# PixelLeaf_RP2040.net
KiCad netlist of a schematic drawn in EAGLE
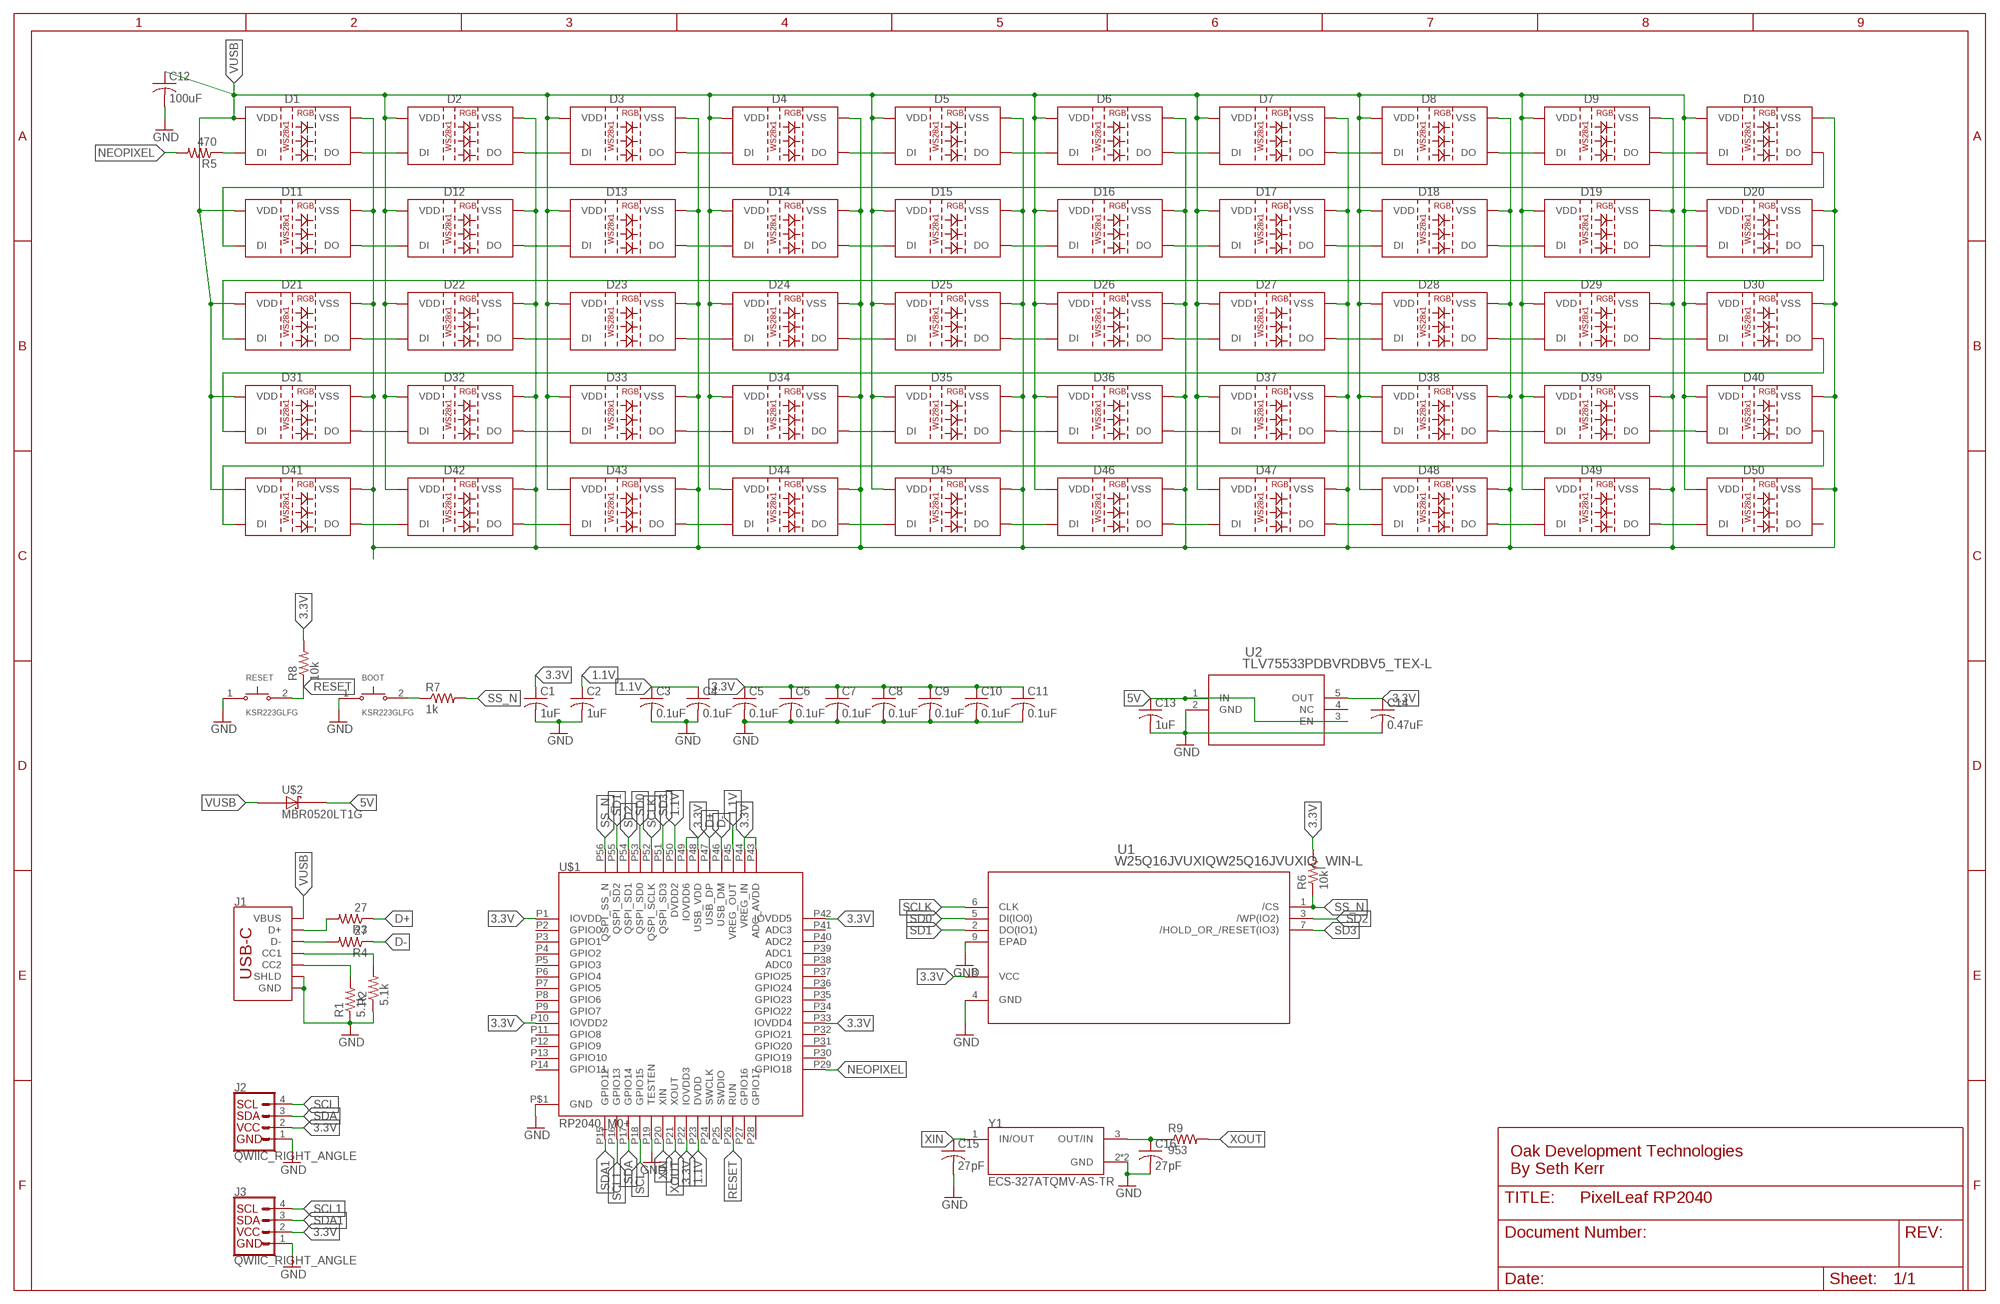
[diagram p0: schematic, sheet 1]

(export (version "E")
  (design (tool "Eeschema 10.0.6"))
  (components
    (comp (ref "BOOT")
      (value "KSR223GLFG")
      (footprint "eagle-import:SW_KSR223GLFG")
      (fields (field (name "MF") "C&K"))
      (libsource (lib "eagle-import") (part "KSR223GLFG"))
    )
    (comp (ref "C1")
      (value "1uF")
      (footprint "eagle-import:C0603")
      (libsource (lib "eagle-import") (part "C-USC0603"))
    )
    (comp (ref "C2")
      (value "1uF")
      (footprint "eagle-import:C0603")
      (libsource (lib "eagle-import") (part "C-USC0603"))
    )
    (comp (ref "C3")
      (value "0.1uF")
      (footprint "eagle-import:C0603")
      (libsource (lib "eagle-import") (part "C-USC0603"))
    )
    (comp (ref "C4")
      (value "0.1uF")
      (footprint "eagle-import:C0603")
      (libsource (lib "eagle-import") (part "C-USC0603"))
    )
    (comp (ref "C5")
      (value "0.1uF")
      (footprint "eagle-import:C0603")
      (libsource (lib "eagle-import") (part "C-USC0603"))
    )
    (comp (ref "C6")
      (value "0.1uF")
      (footprint "eagle-import:C0603")
      (libsource (lib "eagle-import") (part "C-USC0603"))
    )
    (comp (ref "C7")
      (value "0.1uF")
      (footprint "eagle-import:C0603")
      (libsource (lib "eagle-import") (part "C-USC0603"))
    )
    (comp (ref "C8")
      (value "0.1uF")
      (footprint "eagle-import:C0603")
      (libsource (lib "eagle-import") (part "C-USC0603"))
    )
    (comp (ref "C9")
      (value "0.1uF")
      (footprint "eagle-import:C0603")
      (libsource (lib "eagle-import") (part "C-USC0603"))
    )
    (comp (ref "C10")
      (value "0.1uF")
      (footprint "eagle-import:C0603")
      (libsource (lib "eagle-import") (part "C-USC0603"))
    )
    (comp (ref "C11")
      (value "0.1uF")
      (footprint "eagle-import:C0603")
      (libsource (lib "eagle-import") (part "C-USC0603"))
    )
    (comp (ref "C12")
      (value "100uF")
      (footprint "eagle-import:C1206")
      (libsource (lib "eagle-import") (part "C-USC1206"))
    )
    (comp (ref "C13")
      (value "1uF")
      (footprint "eagle-import:C0603")
      (libsource (lib "eagle-import") (part "C-USC0603"))
    )
    (comp (ref "C14")
      (value "0.47uF")
      (footprint "eagle-import:C0603")
      (libsource (lib "eagle-import") (part "C-USC0603"))
    )
    (comp (ref "C15")
      (value "27pF")
      (footprint "eagle-import:C0402")
      (libsource (lib "eagle-import") (part "C-USC0402"))
    )
    (comp (ref "C16")
      (value "27pF")
      (footprint "eagle-import:C0402")
      (libsource (lib "eagle-import") (part "C-USC0402"))
    )
    (comp (ref "D1")
      (value "WS2812BWS2812B-3535")
      (footprint "eagle-import:WS2812-3535")
      (libsource (lib "eagle-import") (part "WS2812BWS2812B-3535"))
    )
    (comp (ref "D2")
      (value "WS2812BWS2812B-3535")
      (footprint "eagle-import:WS2812-3535")
      (libsource (lib "eagle-import") (part "WS2812BWS2812B-3535"))
    )
    (comp (ref "D3")
      (value "WS2812BWS2812B-3535")
      (footprint "eagle-import:WS2812-3535")
      (libsource (lib "eagle-import") (part "WS2812BWS2812B-3535"))
    )
    (comp (ref "D4")
      (value "WS2812BWS2812B-3535")
      (footprint "eagle-import:WS2812-3535")
      (libsource (lib "eagle-import") (part "WS2812BWS2812B-3535"))
    )
    (comp (ref "D5")
      (value "WS2812BWS2812B-3535")
      (footprint "eagle-import:WS2812-3535")
      (libsource (lib "eagle-import") (part "WS2812BWS2812B-3535"))
    )
    (comp (ref "D6")
      (value "WS2812BWS2812B-3535")
      (footprint "eagle-import:WS2812-3535")
      (libsource (lib "eagle-import") (part "WS2812BWS2812B-3535"))
    )
    (comp (ref "D7")
      (value "WS2812BWS2812B-3535")
      (footprint "eagle-import:WS2812-3535")
      (libsource (lib "eagle-import") (part "WS2812BWS2812B-3535"))
    )
    (comp (ref "D8")
      (value "WS2812BWS2812B-3535")
      (footprint "eagle-import:WS2812-3535")
      (libsource (lib "eagle-import") (part "WS2812BWS2812B-3535"))
    )
    (comp (ref "D9")
      (value "WS2812BWS2812B-3535")
      (footprint "eagle-import:WS2812-3535")
      (libsource (lib "eagle-import") (part "WS2812BWS2812B-3535"))
    )
    (comp (ref "D10")
      (value "WS2812BWS2812B-3535")
      (footprint "eagle-import:WS2812-3535")
      (libsource (lib "eagle-import") (part "WS2812BWS2812B-3535"))
    )
    (comp (ref "D11")
      (value "WS2812BWS2812B-3535")
      (footprint "eagle-import:WS2812-3535")
      (libsource (lib "eagle-import") (part "WS2812BWS2812B-3535"))
    )
    (comp (ref "D12")
      (value "WS2812BWS2812B-3535")
      (footprint "eagle-import:WS2812-3535")
      (libsource (lib "eagle-import") (part "WS2812BWS2812B-3535"))
    )
    (comp (ref "D13")
      (value "WS2812BWS2812B-3535")
      (footprint "eagle-import:WS2812-3535")
      (libsource (lib "eagle-import") (part "WS2812BWS2812B-3535"))
    )
    (comp (ref "D14")
      (value "WS2812BWS2812B-3535")
      (footprint "eagle-import:WS2812-3535")
      (libsource (lib "eagle-import") (part "WS2812BWS2812B-3535"))
    )
    (comp (ref "D15")
      (value "WS2812BWS2812B-3535")
      (footprint "eagle-import:WS2812-3535")
      (libsource (lib "eagle-import") (part "WS2812BWS2812B-3535"))
    )
    (comp (ref "D16")
      (value "WS2812BWS2812B-3535")
      (footprint "eagle-import:WS2812-3535")
      (libsource (lib "eagle-import") (part "WS2812BWS2812B-3535"))
    )
    (comp (ref "D17")
      (value "WS2812BWS2812B-3535")
      (footprint "eagle-import:WS2812-3535")
      (libsource (lib "eagle-import") (part "WS2812BWS2812B-3535"))
    )
    (comp (ref "D18")
      (value "WS2812BWS2812B-3535")
      (footprint "eagle-import:WS2812-3535")
      (libsource (lib "eagle-import") (part "WS2812BWS2812B-3535"))
    )
    (comp (ref "D19")
      (value "WS2812BWS2812B-3535")
      (footprint "eagle-import:WS2812-3535")
      (libsource (lib "eagle-import") (part "WS2812BWS2812B-3535"))
    )
    (comp (ref "D20")
      (value "WS2812BWS2812B-3535")
      (footprint "eagle-import:WS2812-3535")
      (libsource (lib "eagle-import") (part "WS2812BWS2812B-3535"))
    )
    (comp (ref "D21")
      (value "WS2812BWS2812B-3535")
      (footprint "eagle-import:WS2812-3535")
      (libsource (lib "eagle-import") (part "WS2812BWS2812B-3535"))
    )
    (comp (ref "D22")
      (value "WS2812BWS2812B-3535")
      (footprint "eagle-import:WS2812-3535")
      (libsource (lib "eagle-import") (part "WS2812BWS2812B-3535"))
    )
    (comp (ref "D23")
      (value "WS2812BWS2812B-3535")
      (footprint "eagle-import:WS2812-3535")
      (libsource (lib "eagle-import") (part "WS2812BWS2812B-3535"))
    )
    (comp (ref "D24")
      (value "WS2812BWS2812B-3535")
      (footprint "eagle-import:WS2812-3535")
      (libsource (lib "eagle-import") (part "WS2812BWS2812B-3535"))
    )
    (comp (ref "D25")
      (value "WS2812BWS2812B-3535")
      (footprint "eagle-import:WS2812-3535")
      (libsource (lib "eagle-import") (part "WS2812BWS2812B-3535"))
    )
    (comp (ref "D26")
      (value "WS2812BWS2812B-3535")
      (footprint "eagle-import:WS2812-3535")
      (libsource (lib "eagle-import") (part "WS2812BWS2812B-3535"))
    )
    (comp (ref "D27")
      (value "WS2812BWS2812B-3535")
      (footprint "eagle-import:WS2812-3535")
      (libsource (lib "eagle-import") (part "WS2812BWS2812B-3535"))
    )
    (comp (ref "D28")
      (value "WS2812BWS2812B-3535")
      (footprint "eagle-import:WS2812-3535")
      (libsource (lib "eagle-import") (part "WS2812BWS2812B-3535"))
    )
    (comp (ref "D29")
      (value "WS2812BWS2812B-3535")
      (footprint "eagle-import:WS2812-3535")
      (libsource (lib "eagle-import") (part "WS2812BWS2812B-3535"))
    )
    (comp (ref "D30")
      (value "WS2812BWS2812B-3535")
      (footprint "eagle-import:WS2812-3535")
      (libsource (lib "eagle-import") (part "WS2812BWS2812B-3535"))
    )
    (comp (ref "D31")
      (value "WS2812BWS2812B-3535")
      (footprint "eagle-import:WS2812-3535")
      (libsource (lib "eagle-import") (part "WS2812BWS2812B-3535"))
    )
    (comp (ref "D32")
      (value "WS2812BWS2812B-3535")
      (footprint "eagle-import:WS2812-3535")
      (libsource (lib "eagle-import") (part "WS2812BWS2812B-3535"))
    )
    (comp (ref "D33")
      (value "WS2812BWS2812B-3535")
      (footprint "eagle-import:WS2812-3535")
      (libsource (lib "eagle-import") (part "WS2812BWS2812B-3535"))
    )
    (comp (ref "D34")
      (value "WS2812BWS2812B-3535")
      (footprint "eagle-import:WS2812-3535")
      (libsource (lib "eagle-import") (part "WS2812BWS2812B-3535"))
    )
    (comp (ref "D35")
      (value "WS2812BWS2812B-3535")
      (footprint "eagle-import:WS2812-3535")
      (libsource (lib "eagle-import") (part "WS2812BWS2812B-3535"))
    )
    (comp (ref "D36")
      (value "WS2812BWS2812B-3535")
      (footprint "eagle-import:WS2812-3535")
      (libsource (lib "eagle-import") (part "WS2812BWS2812B-3535"))
    )
    (comp (ref "D37")
      (value "WS2812BWS2812B-3535")
      (footprint "eagle-import:WS2812-3535")
      (libsource (lib "eagle-import") (part "WS2812BWS2812B-3535"))
    )
    (comp (ref "D38")
      (value "WS2812BWS2812B-3535")
      (footprint "eagle-import:WS2812-3535")
      (libsource (lib "eagle-import") (part "WS2812BWS2812B-3535"))
    )
    (comp (ref "D39")
      (value "WS2812BWS2812B-3535")
      (footprint "eagle-import:WS2812-3535")
      (libsource (lib "eagle-import") (part "WS2812BWS2812B-3535"))
    )
    (comp (ref "D40")
      (value "WS2812BWS2812B-3535")
      (footprint "eagle-import:WS2812-3535")
      (libsource (lib "eagle-import") (part "WS2812BWS2812B-3535"))
    )
    (comp (ref "D41")
      (value "WS2812BWS2812B-3535")
      (footprint "eagle-import:WS2812-3535")
      (libsource (lib "eagle-import") (part "WS2812BWS2812B-3535"))
    )
    (comp (ref "D42")
      (value "WS2812BWS2812B-3535")
      (footprint "eagle-import:WS2812-3535")
      (libsource (lib "eagle-import") (part "WS2812BWS2812B-3535"))
    )
    (comp (ref "D43")
      (value "WS2812BWS2812B-3535")
      (footprint "eagle-import:WS2812-3535")
      (libsource (lib "eagle-import") (part "WS2812BWS2812B-3535"))
    )
    (comp (ref "D44")
      (value "WS2812BWS2812B-3535")
      (footprint "eagle-import:WS2812-3535")
      (libsource (lib "eagle-import") (part "WS2812BWS2812B-3535"))
    )
    (comp (ref "D45")
      (value "WS2812BWS2812B-3535")
      (footprint "eagle-import:WS2812-3535")
      (libsource (lib "eagle-import") (part "WS2812BWS2812B-3535"))
    )
    (comp (ref "D46")
      (value "WS2812BWS2812B-3535")
      (footprint "eagle-import:WS2812-3535")
      (libsource (lib "eagle-import") (part "WS2812BWS2812B-3535"))
    )
    (comp (ref "D47")
      (value "WS2812BWS2812B-3535")
      (footprint "eagle-import:WS2812-3535")
      (libsource (lib "eagle-import") (part "WS2812BWS2812B-3535"))
    )
    (comp (ref "D48")
      (value "WS2812BWS2812B-3535")
      (footprint "eagle-import:WS2812-3535")
      (libsource (lib "eagle-import") (part "WS2812BWS2812B-3535"))
    )
    (comp (ref "D49")
      (value "WS2812BWS2812B-3535")
      (footprint "eagle-import:WS2812-3535")
      (libsource (lib "eagle-import") (part "WS2812BWS2812B-3535"))
    )
    (comp (ref "D50")
      (value "WS2812BWS2812B-3535")
      (footprint "eagle-import:WS2812-3535")
      (libsource (lib "eagle-import") (part "WS2812BWS2812B-3535"))
    )
    (comp (ref "J1")
      (value "USB_C_2-LAYER_PADS")
      (footprint "eagle-import:USB-C-16P-2LAYER-PADS")
      (libsource (lib "eagle-import") (part "USB_C_2-LAYER_PADS"))
    )
    (comp (ref "J2")
      (value "QWIIC_RIGHT_ANGLE")
      (footprint "eagle-import:JST04_1MM_RA")
      (libsource (lib "eagle-import") (part "QWIIC_CONNECTORJS-1MM"))
    )
    (comp (ref "J3")
      (value "QWIIC_RIGHT_ANGLE")
      (footprint "eagle-import:JST04_1MM_RA")
      (libsource (lib "eagle-import") (part "QWIIC_CONNECTORJS-1MM"))
    )
    (comp (ref "R1")
      (value "5.1k")
      (footprint "eagle-import:R0603")
      (libsource (lib "eagle-import") (part "R-US_R0603"))
    )
    (comp (ref "R2")
      (value "5.1k")
      (footprint "eagle-import:R0603")
      (libsource (lib "eagle-import") (part "R-US_R0603"))
    )
    (comp (ref "R3")
      (value "27")
      (footprint "eagle-import:R0603")
      (libsource (lib "eagle-import") (part "R-US_R0603"))
    )
    (comp (ref "R4")
      (value "27")
      (footprint "eagle-import:R0603")
      (libsource (lib "eagle-import") (part "R-US_R0603"))
    )
    (comp (ref "R5")
      (value "470")
      (footprint "eagle-import:R0603")
      (libsource (lib "eagle-import") (part "R-US_R0603"))
    )
    (comp (ref "R6")
      (value "10k")
      (footprint "eagle-import:R0603")
      (libsource (lib "eagle-import") (part "R-US_R0603"))
    )
    (comp (ref "R7")
      (value "1k")
      (footprint "eagle-import:R0603")
      (libsource (lib "eagle-import") (part "R-US_R0603"))
    )
    (comp (ref "R8")
      (value "10k")
      (footprint "eagle-import:R0603")
      (libsource (lib "eagle-import") (part "R-US_R0603"))
    )
    (comp (ref "R9")
      (value "953")
      (footprint "eagle-import:R0402")
      (libsource (lib "eagle-import") (part "R-US_R0402"))
    )
    (comp (ref "RESET")
      (value "KSR223GLFG")
      (footprint "eagle-import:SW_KSR223GLFG")
      (fields (field (name "MF") "C&K"))
      (libsource (lib "eagle-import") (part "KSR223GLFG"))
    )
    (comp (ref "U$1")
      (value "RP2040_M0+")
      (footprint "eagle-import:QFN-56")
      (libsource (lib "eagle-import") (part "RP2040_M0+"))
    )
    (comp (ref "U$2")
      (value "MBR0520LT1G")
      (footprint "eagle-import:SOD3716X117(SOD-123)")
      (fields (field (name "MF") "ON Semiconductor"))
      (libsource (lib "eagle-import") (part "MBR0520LT1G"))
    )
    (comp (ref "U1")
      (value "W25Q16JVUXIQW25Q16JVUXIQ_WIN-L")
      (footprint "eagle-import:W25Q16JVUXIQ_WIN-L")
      (fields
        (field (name "MANUFACTURER_PART_NUMBER") "W25Q16JVUXIQ")
        (field (name "COPYRIGHT") "Copyright (C) 2018 Accelerated Designs. All rights reserved")
      )
      (libsource (lib "eagle-import") (part "W25Q16JVUXIQW25Q16JVUXIQ_WIN-L"))
    )
    (comp (ref "U2")
      (value "TLV75533PDBVRDBV5_TEX-L")
      (footprint "eagle-import:DBV5_TEX-L")
      (fields
        (field (name "MANUFACTURER_PART_NUMBER") "TLV75533PDBVR")
        (field (name "COPYRIGHT") "Copyright (C) 2018 Accelerated Designs. All rights reserved")
      )
      (libsource (lib "eagle-import") (part "TLV75533PDBVRDBV5_TEX-L"))
    )
    (comp (ref "Y1")
      (value "ECS-327ATQMV-AS-TR")
      (footprint "eagle-import:XTAL_ECS-327ATQMV-AS-TR")
      (fields (field (name "DIGI-KEY_PART_NUMBER") "XC2826CT-ND") (field (name "MF") "ECS Inc."))
      (libsource (lib "eagle-import") (part "ECS-327ATQMV-AS-TR"))
    )
  )
  (nets
    (net (code "1") (name "1.1V") (class "Default")
      (node (ref "C2") (pin "1") (pinfunction "1_1") (pintype "passive"))
      (node (ref "C3") (pin "1") (pinfunction "1_1") (pintype "passive"))
      (node (ref "C4") (pin "1") (pinfunction "1_1") (pintype "passive"))
      (node (ref "U$1") (pin "P23") (pinfunction "DVDD_P23") (pintype "bidirectional"))
      (node (ref "U$1") (pin "P45") (pinfunction "VREG_OUT_P45") (pintype "bidirectional"))
      (node (ref "U$1") (pin "P50") (pinfunction "DVDD2_P50") (pintype "bidirectional"))
    )
    (net (code "2") (name "3.3V") (class "Default")
      (node (ref "C1") (pin "1") (pinfunction "1_1") (pintype "passive"))
      (node (ref "C10") (pin "1") (pinfunction "1_1") (pintype "passive"))
      (node (ref "C11") (pin "1") (pinfunction "1_1") (pintype "passive"))
      (node (ref "C14") (pin "1") (pinfunction "1_1") (pintype "passive"))
      (node (ref "C5") (pin "1") (pinfunction "1_1") (pintype "passive"))
      (node (ref "C6") (pin "1") (pinfunction "1_1") (pintype "passive"))
      (node (ref "C7") (pin "1") (pinfunction "1_1") (pintype "passive"))
      (node (ref "C8") (pin "1") (pinfunction "1_1") (pintype "passive"))
      (node (ref "C9") (pin "1") (pinfunction "1_1") (pintype "passive"))
      (node (ref "J2") (pin "2") (pinfunction "2_2") (pintype "power_in"))
      (node (ref "J3") (pin "2") (pinfunction "2_2") (pintype "power_in"))
      (node (ref "R6") (pin "2") (pinfunction "2_2") (pintype "passive"))
      (node (ref "R8") (pin "2") (pinfunction "2_2") (pintype "passive"))
      (node (ref "U$1") (pin "P1") (pinfunction "IOVDD_P1") (pintype "bidirectional"))
      (node (ref "U$1") (pin "P10") (pinfunction "IOVDD2_P10") (pintype "bidirectional"))
      (node (ref "U$1") (pin "P22") (pinfunction "IOVDD3_P22") (pintype "bidirectional"))
      (node (ref "U$1") (pin "P33") (pinfunction "IOVDD4_P33") (pintype "bidirectional"))
      (node (ref "U$1") (pin "P42") (pinfunction "IOVDD5_P42") (pintype "bidirectional"))
      (node (ref "U$1") (pin "P43") (pinfunction "ADC_AVDD_P43") (pintype "bidirectional"))
      (node (ref "U$1") (pin "P44") (pinfunction "VREG_IN_P44") (pintype "bidirectional"))
      (node (ref "U$1") (pin "P48") (pinfunction "USB_VDD_P48") (pintype "bidirectional"))
      (node (ref "U$1") (pin "P49") (pinfunction "IOVDD6_P49") (pintype "bidirectional"))
      (node (ref "U1") (pin "8") (pinfunction "VCC_8") (pintype "passive"))
      (node (ref "U2") (pin "5") (pinfunction "OUT_5") (pintype "output"))
    )
    (net (code "3") (name "5V") (class "Default")
      (node (ref "C13") (pin "1") (pinfunction "1_1") (pintype "passive"))
      (node (ref "U$2") (pin "1") (pinfunction "C_1") (pintype "passive"))
      (node (ref "U2") (pin "1") (pinfunction "IN_1") (pintype "input"))
      (node (ref "U2") (pin "3") (pinfunction "EN_3") (pintype "input"))
    )
    (net (code "4") (name "D+") (class "Default")
      (node (ref "R3") (pin "1") (pinfunction "1_1") (pintype "passive"))
      (node (ref "U$1") (pin "P47") (pinfunction "USB_DP_P47") (pintype "bidirectional"))
    )
    (net (code "5") (name "D-") (class "Default")
      (node (ref "R4") (pin "1") (pinfunction "1_1") (pintype "passive"))
      (node (ref "U$1") (pin "P46") (pinfunction "USB_DM_P46") (pintype "bidirectional"))
    )
    (net (code "6") (name "GND") (class "Default")
      (node (ref "BOOT") (pin "1") (pinfunction "1_1") (pintype "passive"))
      (node (ref "C1") (pin "2") (pinfunction "2_2") (pintype "passive"))
      (node (ref "C10") (pin "2") (pinfunction "2_2") (pintype "passive"))
      (node (ref "C11") (pin "2") (pinfunction "2_2") (pintype "passive"))
      (node (ref "C12") (pin "2") (pinfunction "2_2") (pintype "passive"))
      (node (ref "C13") (pin "2") (pinfunction "2_2") (pintype "passive"))
      (node (ref "C14") (pin "2") (pinfunction "2_2") (pintype "passive"))
      (node (ref "C15") (pin "2") (pinfunction "2_2") (pintype "passive"))
      (node (ref "C16") (pin "2") (pinfunction "2_2") (pintype "passive"))
      (node (ref "C2") (pin "2") (pinfunction "2_2") (pintype "passive"))
      (node (ref "C3") (pin "2") (pinfunction "2_2") (pintype "passive"))
      (node (ref "C4") (pin "2") (pinfunction "2_2") (pintype "passive"))
      (node (ref "C5") (pin "2") (pinfunction "2_2") (pintype "passive"))
      (node (ref "C6") (pin "2") (pinfunction "2_2") (pintype "passive"))
      (node (ref "C7") (pin "2") (pinfunction "2_2") (pintype "passive"))
      (node (ref "C8") (pin "2") (pinfunction "2_2") (pintype "passive"))
      (node (ref "C9") (pin "2") (pinfunction "2_2") (pintype "passive"))
      (node (ref "D1") (pin "VSS") (pinfunction "VSS_VSS") (pintype "bidirectional"))
      (node (ref "D10") (pin "VSS") (pinfunction "VSS_VSS") (pintype "bidirectional"))
      (node (ref "D11") (pin "VSS") (pinfunction "VSS_VSS") (pintype "bidirectional"))
      (node (ref "D12") (pin "VSS") (pinfunction "VSS_VSS") (pintype "bidirectional"))
      (node (ref "D13") (pin "VSS") (pinfunction "VSS_VSS") (pintype "bidirectional"))
      (node (ref "D14") (pin "VSS") (pinfunction "VSS_VSS") (pintype "bidirectional"))
      (node (ref "D15") (pin "VSS") (pinfunction "VSS_VSS") (pintype "bidirectional"))
      (node (ref "D16") (pin "VSS") (pinfunction "VSS_VSS") (pintype "bidirectional"))
      (node (ref "D17") (pin "VSS") (pinfunction "VSS_VSS") (pintype "bidirectional"))
      (node (ref "D18") (pin "VSS") (pinfunction "VSS_VSS") (pintype "bidirectional"))
      (node (ref "D19") (pin "VSS") (pinfunction "VSS_VSS") (pintype "bidirectional"))
      (node (ref "D2") (pin "VSS") (pinfunction "VSS_VSS") (pintype "bidirectional"))
      (node (ref "D20") (pin "VSS") (pinfunction "VSS_VSS") (pintype "bidirectional"))
      (node (ref "D21") (pin "VSS") (pinfunction "VSS_VSS") (pintype "bidirectional"))
      (node (ref "D22") (pin "VSS") (pinfunction "VSS_VSS") (pintype "bidirectional"))
      (node (ref "D23") (pin "VSS") (pinfunction "VSS_VSS") (pintype "bidirectional"))
      (node (ref "D24") (pin "VSS") (pinfunction "VSS_VSS") (pintype "bidirectional"))
      (node (ref "D25") (pin "VSS") (pinfunction "VSS_VSS") (pintype "bidirectional"))
      (node (ref "D26") (pin "VSS") (pinfunction "VSS_VSS") (pintype "bidirectional"))
      (node (ref "D27") (pin "VSS") (pinfunction "VSS_VSS") (pintype "bidirectional"))
      (node (ref "D28") (pin "VSS") (pinfunction "VSS_VSS") (pintype "bidirectional"))
      (node (ref "D29") (pin "VSS") (pinfunction "VSS_VSS") (pintype "bidirectional"))
      (node (ref "D3") (pin "VSS") (pinfunction "VSS_VSS") (pintype "bidirectional"))
      (node (ref "D30") (pin "VSS") (pinfunction "VSS_VSS") (pintype "bidirectional"))
      (node (ref "D31") (pin "VSS") (pinfunction "VSS_VSS") (pintype "bidirectional"))
      (node (ref "D32") (pin "VSS") (pinfunction "VSS_VSS") (pintype "bidirectional"))
      (node (ref "D33") (pin "VSS") (pinfunction "VSS_VSS") (pintype "bidirectional"))
      (node (ref "D34") (pin "VSS") (pinfunction "VSS_VSS") (pintype "bidirectional"))
      (node (ref "D35") (pin "VSS") (pinfunction "VSS_VSS") (pintype "bidirectional"))
      (node (ref "D36") (pin "VSS") (pinfunction "VSS_VSS") (pintype "bidirectional"))
      (node (ref "D37") (pin "VSS") (pinfunction "VSS_VSS") (pintype "bidirectional"))
      (node (ref "D38") (pin "VSS") (pinfunction "VSS_VSS") (pintype "bidirectional"))
      (node (ref "D39") (pin "VSS") (pinfunction "VSS_VSS") (pintype "bidirectional"))
      (node (ref "D4") (pin "VSS") (pinfunction "VSS_VSS") (pintype "bidirectional"))
      (node (ref "D40") (pin "VSS") (pinfunction "VSS_VSS") (pintype "bidirectional"))
      (node (ref "D41") (pin "VSS") (pinfunction "VSS_VSS") (pintype "bidirectional"))
      (node (ref "D42") (pin "VSS") (pinfunction "VSS_VSS") (pintype "bidirectional"))
      (node (ref "D43") (pin "VSS") (pinfunction "VSS_VSS") (pintype "bidirectional"))
      (node (ref "D44") (pin "VSS") (pinfunction "VSS_VSS") (pintype "bidirectional"))
      (node (ref "D45") (pin "VSS") (pinfunction "VSS_VSS") (pintype "bidirectional"))
      (node (ref "D46") (pin "VSS") (pinfunction "VSS_VSS") (pintype "bidirectional"))
      (node (ref "D47") (pin "VSS") (pinfunction "VSS_VSS") (pintype "bidirectional"))
      (node (ref "D48") (pin "VSS") (pinfunction "VSS_VSS") (pintype "bidirectional"))
      (node (ref "D49") (pin "VSS") (pinfunction "VSS_VSS") (pintype "bidirectional"))
      (node (ref "D5") (pin "VSS") (pinfunction "VSS_VSS") (pintype "bidirectional"))
      (node (ref "D50") (pin "VSS") (pinfunction "VSS_VSS") (pintype "bidirectional"))
      (node (ref "D6") (pin "VSS") (pinfunction "VSS_VSS") (pintype "bidirectional"))
      (node (ref "D7") (pin "VSS") (pinfunction "VSS_VSS") (pintype "bidirectional"))
      (node (ref "D8") (pin "VSS") (pinfunction "VSS_VSS") (pintype "bidirectional"))
      (node (ref "D9") (pin "VSS") (pinfunction "VSS_VSS") (pintype "bidirectional"))
      (node (ref "J1") (pin "GND") (pinfunction "GND_GND") (pintype "bidirectional"))
      (node (ref "J1") (pin "GND2") (pinfunction "GND_GND2") (pintype "bidirectional"))
      (node (ref "J1") (pin "P$1") (pinfunction "SHLD_P$1") (pintype "bidirectional"))
      (node (ref "J1") (pin "P$2") (pinfunction "SHLD_P$2") (pintype "bidirectional"))
      (node (ref "J1") (pin "P$3") (pinfunction "SHLD_P$3") (pintype "bidirectional"))
      (node (ref "J1") (pin "P$4") (pinfunction "SHLD_P$4") (pintype "bidirectional"))
      (node (ref "J1") (pin "SHLD1") (pinfunction "SHLD_SHLD1") (pintype "bidirectional"))
      (node (ref "J1") (pin "SHLD2") (pinfunction "SHLD_SHLD2") (pintype "bidirectional"))
      (node (ref "J1") (pin "SHLD3") (pinfunction "SHLD_SHLD3") (pintype "bidirectional"))
      (node (ref "J1") (pin "SHLD4") (pinfunction "SHLD_SHLD4") (pintype "bidirectional"))
      (node (ref "J2") (pin "1") (pinfunction "1_1") (pintype "power_in"))
      (node (ref "J3") (pin "1") (pinfunction "1_1") (pintype "power_in"))
      (node (ref "R1") (pin "1") (pinfunction "1_1") (pintype "passive"))
      (node (ref "R2") (pin "1") (pinfunction "1_1") (pintype "passive"))
      (node (ref "RESET") (pin "1") (pinfunction "1_1") (pintype "passive"))
      (node (ref "U$1") (pin "P$1") (pinfunction "GND_P$1") (pintype "bidirectional"))
      (node (ref "U$1") (pin "P19") (pinfunction "TESTEN_P19") (pintype "bidirectional"))
      (node (ref "U1") (pin "4") (pinfunction "GND_4") (pintype "passive"))
      (node (ref "U1") (pin "9") (pinfunction "EPAD_9") (pintype "passive"))
      (node (ref "U2") (pin "2") (pinfunction "GND_2") (pintype "power_in"))
      (node (ref "Y1") (pin "2") (pinfunction "GND_2") (pintype "power_in"))
      (node (ref "Y1") (pin "4") (pinfunction "GND_4") (pintype "power_in"))
    )
    (net (code "7") (name "NEOPIXEL") (class "Default")
      (node (ref "R5") (pin "2") (pinfunction "2_2") (pintype "passive"))
      (node (ref "U$1") (pin "P29") (pinfunction "GPIO18_P29") (pintype "bidirectional"))
    )
    (net (code "8") (name "Net-(BOOT-Pad2)") (class "Default")
      (node (ref "BOOT") (pin "2") (pinfunction "2_2") (pintype "passive"))
      (node (ref "R7") (pin "1") (pinfunction "1_1") (pintype "passive"))
    )
    (net (code "9") (name "Net-(D1-DI)") (class "Default")
      (node (ref "D1") (pin "DIN") (pinfunction "DI_DIN") (pintype "bidirectional"))
      (node (ref "R5") (pin "1") (pinfunction "1_1") (pintype "passive"))
    )
    (net (code "10") (name "Net-(D1-DO)") (class "Default")
      (node (ref "D1") (pin "DOUT") (pinfunction "DO_DOUT") (pintype "bidirectional"))
      (node (ref "D2") (pin "DIN") (pinfunction "DI_DIN") (pintype "bidirectional"))
    )
    (net (code "11") (name "Net-(D2-DO)") (class "Default")
      (node (ref "D2") (pin "DOUT") (pinfunction "DO_DOUT") (pintype "bidirectional"))
      (node (ref "D3") (pin "DIN") (pinfunction "DI_DIN") (pintype "bidirectional"))
    )
    (net (code "12") (name "Net-(D3-DO)") (class "Default")
      (node (ref "D3") (pin "DOUT") (pinfunction "DO_DOUT") (pintype "bidirectional"))
      (node (ref "D4") (pin "DIN") (pinfunction "DI_DIN") (pintype "bidirectional"))
    )
    (net (code "13") (name "Net-(D4-DO)") (class "Default")
      (node (ref "D4") (pin "DOUT") (pinfunction "DO_DOUT") (pintype "bidirectional"))
      (node (ref "D5") (pin "DIN") (pinfunction "DI_DIN") (pintype "bidirectional"))
    )
    (net (code "14") (name "Net-(D5-DO)") (class "Default")
      (node (ref "D5") (pin "DOUT") (pinfunction "DO_DOUT") (pintype "bidirectional"))
      (node (ref "D6") (pin "DIN") (pinfunction "DI_DIN") (pintype "bidirectional"))
    )
    (net (code "15") (name "Net-(D6-DO)") (class "Default")
      (node (ref "D6") (pin "DOUT") (pinfunction "DO_DOUT") (pintype "bidirectional"))
      (node (ref "D7") (pin "DIN") (pinfunction "DI_DIN") (pintype "bidirectional"))
    )
    (net (code "16") (name "Net-(D7-DO)") (class "Default")
      (node (ref "D7") (pin "DOUT") (pinfunction "DO_DOUT") (pintype "bidirectional"))
      (node (ref "D8") (pin "DIN") (pinfunction "DI_DIN") (pintype "bidirectional"))
    )
    (net (code "17") (name "Net-(D8-DO)") (class "Default")
      (node (ref "D8") (pin "DOUT") (pinfunction "DO_DOUT") (pintype "bidirectional"))
      (node (ref "D9") (pin "DIN") (pinfunction "DI_DIN") (pintype "bidirectional"))
    )
    (net (code "18") (name "Net-(D10-DI)") (class "Default")
      (node (ref "D10") (pin "DIN") (pinfunction "DI_DIN") (pintype "bidirectional"))
      (node (ref "D9") (pin "DOUT") (pinfunction "DO_DOUT") (pintype "bidirectional"))
    )
    (net (code "19") (name "Net-(D10-DO)") (class "Default")
      (node (ref "D10") (pin "DOUT") (pinfunction "DO_DOUT") (pintype "bidirectional"))
      (node (ref "D11") (pin "DIN") (pinfunction "DI_DIN") (pintype "bidirectional"))
    )
    (net (code "20") (name "Net-(D11-DO)") (class "Default")
      (node (ref "D11") (pin "DOUT") (pinfunction "DO_DOUT") (pintype "bidirectional"))
      (node (ref "D12") (pin "DIN") (pinfunction "DI_DIN") (pintype "bidirectional"))
    )
    (net (code "21") (name "Net-(D12-DO)") (class "Default")
      (node (ref "D12") (pin "DOUT") (pinfunction "DO_DOUT") (pintype "bidirectional"))
      (node (ref "D13") (pin "DIN") (pinfunction "DI_DIN") (pintype "bidirectional"))
    )
    (net (code "22") (name "Net-(D13-DO)") (class "Default")
      (node (ref "D13") (pin "DOUT") (pinfunction "DO_DOUT") (pintype "bidirectional"))
      (node (ref "D14") (pin "DIN") (pinfunction "DI_DIN") (pintype "bidirectional"))
    )
    (net (code "23") (name "Net-(D14-DO)") (class "Default")
      (node (ref "D14") (pin "DOUT") (pinfunction "DO_DOUT") (pintype "bidirectional"))
      (node (ref "D15") (pin "DIN") (pinfunction "DI_DIN") (pintype "bidirectional"))
    )
    (net (code "24") (name "Net-(D15-DO)") (class "Default")
      (node (ref "D15") (pin "DOUT") (pinfunction "DO_DOUT") (pintype "bidirectional"))
      (node (ref "D16") (pin "DIN") (pinfunction "DI_DIN") (pintype "bidirectional"))
    )
    (net (code "25") (name "Net-(D16-DO)") (class "Default")
      (node (ref "D16") (pin "DOUT") (pinfunction "DO_DOUT") (pintype "bidirectional"))
      (node (ref "D17") (pin "DIN") (pinfunction "DI_DIN") (pintype "bidirectional"))
    )
    (net (code "26") (name "Net-(D17-DO)") (class "Default")
      (node (ref "D17") (pin "DOUT") (pinfunction "DO_DOUT") (pintype "bidirectional"))
      (node (ref "D18") (pin "DIN") (pinfunction "DI_DIN") (pintype "bidirectional"))
    )
    (net (code "27") (name "Net-(D18-DO)") (class "Default")
      (node (ref "D18") (pin "DOUT") (pinfunction "DO_DOUT") (pintype "bidirectional"))
      (node (ref "D19") (pin "DIN") (pinfunction "DI_DIN") (pintype "bidirectional"))
    )
    (net (code "28") (name "Net-(D19-DO)") (class "Default")
      (node (ref "D19") (pin "DOUT") (pinfunction "DO_DOUT") (pintype "bidirectional"))
      (node (ref "D20") (pin "DIN") (pinfunction "DI_DIN") (pintype "bidirectional"))
    )
    (net (code "29") (name "Net-(D20-DO)") (class "Default")
      (node (ref "D20") (pin "DOUT") (pinfunction "DO_DOUT") (pintype "bidirectional"))
      (node (ref "D21") (pin "DIN") (pinfunction "DI_DIN") (pintype "bidirectional"))
    )
    (net (code "30") (name "Net-(D21-DO)") (class "Default")
      (node (ref "D21") (pin "DOUT") (pinfunction "DO_DOUT") (pintype "bidirectional"))
      (node (ref "D22") (pin "DIN") (pinfunction "DI_DIN") (pintype "bidirectional"))
    )
    (net (code "31") (name "Net-(D22-DO)") (class "Default")
      (node (ref "D22") (pin "DOUT") (pinfunction "DO_DOUT") (pintype "bidirectional"))
      (node (ref "D23") (pin "DIN") (pinfunction "DI_DIN") (pintype "bidirectional"))
    )
    (net (code "32") (name "Net-(D23-DO)") (class "Default")
      (node (ref "D23") (pin "DOUT") (pinfunction "DO_DOUT") (pintype "bidirectional"))
      (node (ref "D24") (pin "DIN") (pinfunction "DI_DIN") (pintype "bidirectional"))
    )
    (net (code "33") (name "Net-(D24-DO)") (class "Default")
      (node (ref "D24") (pin "DOUT") (pinfunction "DO_DOUT") (pintype "bidirectional"))
      (node (ref "D25") (pin "DIN") (pinfunction "DI_DIN") (pintype "bidirectional"))
    )
    (net (code "34") (name "Net-(D25-DO)") (class "Default")
      (node (ref "D25") (pin "DOUT") (pinfunction "DO_DOUT") (pintype "bidirectional"))
      (node (ref "D26") (pin "DIN") (pinfunction "DI_DIN") (pintype "bidirectional"))
    )
    (net (code "35") (name "Net-(D26-DO)") (class "Default")
      (node (ref "D26") (pin "DOUT") (pinfunction "DO_DOUT") (pintype "bidirectional"))
      (node (ref "D27") (pin "DIN") (pinfunction "DI_DIN") (pintype "bidirectional"))
    )
    (net (code "36") (name "Net-(D27-DO)") (class "Default")
      (node (ref "D27") (pin "DOUT") (pinfunction "DO_DOUT") (pintype "bidirectional"))
      (node (ref "D28") (pin "DIN") (pinfunction "DI_DIN") (pintype "bidirectional"))
    )
    (net (code "37") (name "Net-(D28-DO)") (class "Default")
      (node (ref "D28") (pin "DOUT") (pinfunction "DO_DOUT") (pintype "bidirectional"))
      (node (ref "D29") (pin "DIN") (pinfunction "DI_DIN") (pintype "bidirectional"))
    )
    (net (code "38") (name "Net-(D29-DO)") (class "Default")
      (node (ref "D29") (pin "DOUT") (pinfunction "DO_DOUT") (pintype "bidirectional"))
      (node (ref "D30") (pin "DIN") (pinfunction "DI_DIN") (pintype "bidirectional"))
    )
    (net (code "39") (name "Net-(D30-DO)") (class "Default")
      (node (ref "D30") (pin "DOUT") (pinfunction "DO_DOUT") (pintype "bidirectional"))
      (node (ref "D31") (pin "DIN") (pinfunction "DI_DIN") (pintype "bidirectional"))
    )
    (net (code "40") (name "Net-(D31-DO)") (class "Default")
      (node (ref "D31") (pin "DOUT") (pinfunction "DO_DOUT") (pintype "bidirectional"))
      (node (ref "D32") (pin "DIN") (pinfunction "DI_DIN") (pintype "bidirectional"))
    )
    (net (code "41") (name "Net-(D32-DO)") (class "Default")
      (node (ref "D32") (pin "DOUT") (pinfunction "DO_DOUT") (pintype "bidirectional"))
      (node (ref "D33") (pin "DIN") (pinfunction "DI_DIN") (pintype "bidirectional"))
    )
    (net (code "42") (name "Net-(D33-DO)") (class "Default")
      (node (ref "D33") (pin "DOUT") (pinfunction "DO_DOUT") (pintype "bidirectional"))
      (node (ref "D34") (pin "DIN") (pinfunction "DI_DIN") (pintype "bidirectional"))
    )
    (net (code "43") (name "Net-(D34-DO)") (class "Default")
      (node (ref "D34") (pin "DOUT") (pinfunction "DO_DOUT") (pintype "bidirectional"))
      (node (ref "D35") (pin "DIN") (pinfunction "DI_DIN") (pintype "bidirectional"))
    )
    (net (code "44") (name "Net-(D35-DO)") (class "Default")
      (node (ref "D35") (pin "DOUT") (pinfunction "DO_DOUT") (pintype "bidirectional"))
      (node (ref "D36") (pin "DIN") (pinfunction "DI_DIN") (pintype "bidirectional"))
    )
    (net (code "45") (name "Net-(D36-DO)") (class "Default")
      (node (ref "D36") (pin "DOUT") (pinfunction "DO_DOUT") (pintype "bidirectional"))
      (node (ref "D37") (pin "DIN") (pinfunction "DI_DIN") (pintype "bidirectional"))
    )
    (net (code "46") (name "Net-(D37-DO)") (class "Default")
      (node (ref "D37") (pin "DOUT") (pinfunction "DO_DOUT") (pintype "bidirectional"))
      (node (ref "D38") (pin "DIN") (pinfunction "DI_DIN") (pintype "bidirectional"))
    )
    (net (code "47") (name "Net-(D38-DO)") (class "Default")
      (node (ref "D38") (pin "DOUT") (pinfunction "DO_DOUT") (pintype "bidirectional"))
      (node (ref "D39") (pin "DIN") (pinfunction "DI_DIN") (pintype "bidirectional"))
    )
    (net (code "48") (name "Net-(D39-DO)") (class "Default")
      (node (ref "D39") (pin "DOUT") (pinfunction "DO_DOUT") (pintype "bidirectional"))
      (node (ref "D40") (pin "DIN") (pinfunction "DI_DIN") (pintype "bidirectional"))
    )
    (net (code "49") (name "Net-(D40-DO)") (class "Default")
      (node (ref "D40") (pin "DOUT") (pinfunction "DO_DOUT") (pintype "bidirectional"))
      (node (ref "D41") (pin "DIN") (pinfunction "DI_DIN") (pintype "bidirectional"))
    )
    (net (code "50") (name "Net-(D41-DO)") (class "Default")
      (node (ref "D41") (pin "DOUT") (pinfunction "DO_DOUT") (pintype "bidirectional"))
      (node (ref "D42") (pin "DIN") (pinfunction "DI_DIN") (pintype "bidirectional"))
    )
    (net (code "51") (name "Net-(D42-DO)") (class "Default")
      (node (ref "D42") (pin "DOUT") (pinfunction "DO_DOUT") (pintype "bidirectional"))
      (node (ref "D43") (pin "DIN") (pinfunction "DI_DIN") (pintype "bidirectional"))
    )
    (net (code "52") (name "Net-(D43-DO)") (class "Default")
      (node (ref "D43") (pin "DOUT") (pinfunction "DO_DOUT") (pintype "bidirectional"))
      (node (ref "D44") (pin "DIN") (pinfunction "DI_DIN") (pintype "bidirectional"))
    )
    (net (code "53") (name "Net-(D44-DO)") (class "Default")
      (node (ref "D44") (pin "DOUT") (pinfunction "DO_DOUT") (pintype "bidirectional"))
      (node (ref "D45") (pin "DIN") (pinfunction "DI_DIN") (pintype "bidirectional"))
    )
    (net (code "54") (name "Net-(D45-DO)") (class "Default")
      (node (ref "D45") (pin "DOUT") (pinfunction "DO_DOUT") (pintype "bidirectional"))
      (node (ref "D46") (pin "DIN") (pinfunction "DI_DIN") (pintype "bidirectional"))
    )
    (net (code "55") (name "Net-(D46-DO)") (class "Default")
      (node (ref "D46") (pin "DOUT") (pinfunction "DO_DOUT") (pintype "bidirectional"))
      (node (ref "D47") (pin "DIN") (pinfunction "DI_DIN") (pintype "bidirectional"))
    )
    (net (code "56") (name "Net-(D47-DO)") (class "Default")
      (node (ref "D47") (pin "DOUT") (pinfunction "DO_DOUT") (pintype "bidirectional"))
      (node (ref "D48") (pin "DIN") (pinfunction "DI_DIN") (pintype "bidirectional"))
    )
    (net (code "57") (name "Net-(D48-DO)") (class "Default")
      (node (ref "D48") (pin "DOUT") (pinfunction "DO_DOUT") (pintype "bidirectional"))
      (node (ref "D49") (pin "DIN") (pinfunction "DI_DIN") (pintype "bidirectional"))
    )
    (net (code "58") (name "Net-(D49-DO)") (class "Default")
      (node (ref "D49") (pin "DOUT") (pinfunction "DO_DOUT") (pintype "bidirectional"))
      (node (ref "D50") (pin "DIN") (pinfunction "DI_DIN") (pintype "bidirectional"))
    )
    (net (code "59") (name "Net-(J1-CC1)") (class "Default")
      (node (ref "J1") (pin "A5") (pinfunction "CC1_A5") (pintype "bidirectional"))
      (node (ref "R2") (pin "2") (pinfunction "2_2") (pintype "passive"))
    )
    (net (code "60") (name "Net-(J1-CC2)") (class "Default")
      (node (ref "J1") (pin "B5") (pinfunction "CC2_B5") (pintype "bidirectional"))
      (node (ref "R1") (pin "2") (pinfunction "2_2") (pintype "passive"))
    )
    (net (code "61") (name "Net-(J1-D+-PadA6)") (class "Default")
      (node (ref "J1") (pin "A6") (pinfunction "D+_A6") (pintype "bidirectional"))
      (node (ref "J1") (pin "B6") (pinfunction "D+_B6") (pintype "bidirectional"))
      (node (ref "R3") (pin "2") (pinfunction "2_2") (pintype "passive"))
    )
    (net (code "62") (name "Net-(J1-D--PadA7)") (class "Default")
      (node (ref "J1") (pin "A7") (pinfunction "D-_A7") (pintype "bidirectional"))
      (node (ref "J1") (pin "B7") (pinfunction "D-_B7") (pintype "bidirectional"))
      (node (ref "R4") (pin "2") (pinfunction "2_2") (pintype "passive"))
    )
    (net (code "63") (name "Net-(Y1-OUT{slash}IN)") (class "Default")
      (node (ref "C16") (pin "1") (pinfunction "1_1") (pintype "passive"))
      (node (ref "R9") (pin "1") (pinfunction "1_1") (pintype "passive"))
      (node (ref "Y1") (pin "3") (pinfunction "OUT/IN_3") (pintype "bidirectional"))
    )
    (net (code "64") (name "RESET") (class "Default")
      (node (ref "R8") (pin "1") (pinfunction "1_1") (pintype "passive"))
      (node (ref "RESET") (pin "2") (pinfunction "2_2") (pintype "passive"))
      (node (ref "U$1") (pin "P26") (pinfunction "RUN_P26") (pintype "bidirectional"))
    )
    (net (code "65") (name "SCL") (class "Default")
      (node (ref "J2") (pin "4") (pinfunction "4_4") (pintype "passive"))
      (node (ref "U$1") (pin "P18") (pinfunction "GPIO15_P18") (pintype "bidirectional"))
    )
    (net (code "66") (name "SCL1") (class "Default")
      (node (ref "J3") (pin "4") (pinfunction "4_4") (pintype "passive"))
      (node (ref "U$1") (pin "P16") (pinfunction "GPIO13_P16") (pintype "bidirectional"))
    )
    (net (code "67") (name "SCLK") (class "Default")
      (node (ref "U$1") (pin "P52") (pinfunction "QSPI_SCLK_P52") (pintype "bidirectional"))
      (node (ref "U1") (pin "6") (pinfunction "CLK_6") (pintype "passive"))
    )
    (net (code "68") (name "SD0") (class "Default")
      (node (ref "U$1") (pin "P53") (pinfunction "QSPI_SD0_P53") (pintype "bidirectional"))
      (node (ref "U1") (pin "5") (pinfunction "DI(IO0)_5") (pintype "passive"))
    )
    (net (code "69") (name "SD1") (class "Default")
      (node (ref "U$1") (pin "P55") (pinfunction "QSPI_SD2_P55") (pintype "bidirectional"))
      (node (ref "U1") (pin "2") (pinfunction "DO(IO1)_2") (pintype "passive"))
    )
    (net (code "70") (name "SD2") (class "Default")
      (node (ref "U$1") (pin "P54") (pinfunction "QSPI_SD1_P54") (pintype "bidirectional"))
      (node (ref "U1") (pin "3") (pinfunction "/WP(IO2)_3") (pintype "passive"))
    )
    (net (code "71") (name "SD3") (class "Default")
      (node (ref "U$1") (pin "P51") (pinfunction "QSPI_SD3_P51") (pintype "bidirectional"))
      (node (ref "U1") (pin "7") (pinfunction "/HOLD_OR_/RESET(IO3)_7") (pintype "passive"))
    )
    (net (code "72") (name "SDA") (class "Default")
      (node (ref "J2") (pin "3") (pinfunction "3_3") (pintype "passive"))
      (node (ref "U$1") (pin "P17") (pinfunction "GPIO14_P17") (pintype "bidirectional"))
    )
    (net (code "73") (name "SDA1") (class "Default")
      (node (ref "J3") (pin "3") (pinfunction "3_3") (pintype "passive"))
      (node (ref "U$1") (pin "P15") (pinfunction "GPIO12_P15") (pintype "bidirectional"))
    )
    (net (code "74") (name "SS_N") (class "Default")
      (node (ref "R6") (pin "1") (pinfunction "1_1") (pintype "passive"))
      (node (ref "R7") (pin "2") (pinfunction "2_2") (pintype "passive"))
      (node (ref "U$1") (pin "P56") (pinfunction "QSPI_SS_N_P56") (pintype "bidirectional"))
      (node (ref "U1") (pin "1") (pinfunction "/CS_1") (pintype "passive"))
    )
    (net (code "75") (name "VUSB") (class "Default")
      (node (ref "C12") (pin "1") (pinfunction "1_1") (pintype "passive"))
      (node (ref "D1") (pin "VDD") (pinfunction "VDD_VDD") (pintype "bidirectional"))
      (node (ref "D10") (pin "VDD") (pinfunction "VDD_VDD") (pintype "bidirectional"))
      (node (ref "D11") (pin "VDD") (pinfunction "VDD_VDD") (pintype "bidirectional"))
      (node (ref "D12") (pin "VDD") (pinfunction "VDD_VDD") (pintype "bidirectional"))
      (node (ref "D13") (pin "VDD") (pinfunction "VDD_VDD") (pintype "bidirectional"))
      (node (ref "D14") (pin "VDD") (pinfunction "VDD_VDD") (pintype "bidirectional"))
      (node (ref "D15") (pin "VDD") (pinfunction "VDD_VDD") (pintype "bidirectional"))
      (node (ref "D16") (pin "VDD") (pinfunction "VDD_VDD") (pintype "bidirectional"))
      (node (ref "D17") (pin "VDD") (pinfunction "VDD_VDD") (pintype "bidirectional"))
      (node (ref "D18") (pin "VDD") (pinfunction "VDD_VDD") (pintype "bidirectional"))
      (node (ref "D19") (pin "VDD") (pinfunction "VDD_VDD") (pintype "bidirectional"))
      (node (ref "D2") (pin "VDD") (pinfunction "VDD_VDD") (pintype "bidirectional"))
      (node (ref "D20") (pin "VDD") (pinfunction "VDD_VDD") (pintype "bidirectional"))
      (node (ref "D21") (pin "VDD") (pinfunction "VDD_VDD") (pintype "bidirectional"))
      (node (ref "D22") (pin "VDD") (pinfunction "VDD_VDD") (pintype "bidirectional"))
      (node (ref "D23") (pin "VDD") (pinfunction "VDD_VDD") (pintype "bidirectional"))
      (node (ref "D24") (pin "VDD") (pinfunction "VDD_VDD") (pintype "bidirectional"))
      (node (ref "D25") (pin "VDD") (pinfunction "VDD_VDD") (pintype "bidirectional"))
      (node (ref "D26") (pin "VDD") (pinfunction "VDD_VDD") (pintype "bidirectional"))
      (node (ref "D27") (pin "VDD") (pinfunction "VDD_VDD") (pintype "bidirectional"))
      (node (ref "D28") (pin "VDD") (pinfunction "VDD_VDD") (pintype "bidirectional"))
      (node (ref "D29") (pin "VDD") (pinfunction "VDD_VDD") (pintype "bidirectional"))
      (node (ref "D3") (pin "VDD") (pinfunction "VDD_VDD") (pintype "bidirectional"))
      (node (ref "D30") (pin "VDD") (pinfunction "VDD_VDD") (pintype "bidirectional"))
      (node (ref "D31") (pin "VDD") (pinfunction "VDD_VDD") (pintype "bidirectional"))
      (node (ref "D32") (pin "VDD") (pinfunction "VDD_VDD") (pintype "bidirectional"))
      (node (ref "D33") (pin "VDD") (pinfunction "VDD_VDD") (pintype "bidirectional"))
      (node (ref "D34") (pin "VDD") (pinfunction "VDD_VDD") (pintype "bidirectional"))
      (node (ref "D35") (pin "VDD") (pinfunction "VDD_VDD") (pintype "bidirectional"))
      (node (ref "D36") (pin "VDD") (pinfunction "VDD_VDD") (pintype "bidirectional"))
      (node (ref "D37") (pin "VDD") (pinfunction "VDD_VDD") (pintype "bidirectional"))
      (node (ref "D38") (pin "VDD") (pinfunction "VDD_VDD") (pintype "bidirectional"))
      (node (ref "D39") (pin "VDD") (pinfunction "VDD_VDD") (pintype "bidirectional"))
      (node (ref "D4") (pin "VDD") (pinfunction "VDD_VDD") (pintype "bidirectional"))
      (node (ref "D40") (pin "VDD") (pinfunction "VDD_VDD") (pintype "bidirectional"))
      (node (ref "D41") (pin "VDD") (pinfunction "VDD_VDD") (pintype "bidirectional"))
      (node (ref "D42") (pin "VDD") (pinfunction "VDD_VDD") (pintype "bidirectional"))
      (node (ref "D43") (pin "VDD") (pinfunction "VDD_VDD") (pintype "bidirectional"))
      (node (ref "D44") (pin "VDD") (pinfunction "VDD_VDD") (pintype "bidirectional"))
      (node (ref "D45") (pin "VDD") (pinfunction "VDD_VDD") (pintype "bidirectional"))
      (node (ref "D46") (pin "VDD") (pinfunction "VDD_VDD") (pintype "bidirectional"))
      (node (ref "D47") (pin "VDD") (pinfunction "VDD_VDD") (pintype "bidirectional"))
      (node (ref "D48") (pin "VDD") (pinfunction "VDD_VDD") (pintype "bidirectional"))
      (node (ref "D49") (pin "VDD") (pinfunction "VDD_VDD") (pintype "bidirectional"))
      (node (ref "D5") (pin "VDD") (pinfunction "VDD_VDD") (pintype "bidirectional"))
      (node (ref "D50") (pin "VDD") (pinfunction "VDD_VDD") (pintype "bidirectional"))
      (node (ref "D6") (pin "VDD") (pinfunction "VDD_VDD") (pintype "bidirectional"))
      (node (ref "D7") (pin "VDD") (pinfunction "VDD_VDD") (pintype "bidirectional"))
      (node (ref "D8") (pin "VDD") (pinfunction "VDD_VDD") (pintype "bidirectional"))
      (node (ref "D9") (pin "VDD") (pinfunction "VDD_VDD") (pintype "bidirectional"))
      (node (ref "J1") (pin "VBUS1") (pinfunction "VBUS_VBUS1") (pintype "bidirectional"))
      (node (ref "J1") (pin "VBUS2") (pinfunction "VBUS_VBUS2") (pintype "bidirectional"))
      (node (ref "U$2") (pin "2") (pinfunction "A_2") (pintype "passive"))
    )
    (net (code "76") (name "XIN") (class "Default")
      (node (ref "C15") (pin "1") (pinfunction "1_1") (pintype "passive"))
      (node (ref "U$1") (pin "P20") (pinfunction "XIN_P20") (pintype "bidirectional"))
      (node (ref "Y1") (pin "1") (pinfunction "IN/OUT_1") (pintype "bidirectional"))
    )
    (net (code "77") (name "XOUT") (class "Default")
      (node (ref "R9") (pin "2") (pinfunction "2_2") (pintype "passive"))
      (node (ref "U$1") (pin "P21") (pinfunction "XOUT_P21") (pintype "bidirectional"))
    )
    (net (code "78") (name "unconnected-(D50-DO-PadDOUT)") (class "Default")
      (node (ref "D50") (pin "DOUT") (pinfunction "DO_DOUT") (pintype "bidirectional"))
    )
    (net (code "79") (name "unconnected-(U$1-ADC0-PadP38)") (class "Default")
      (node (ref "U$1") (pin "P38") (pinfunction "ADC0_P38") (pintype "bidirectional"))
    )
    (net (code "80") (name "unconnected-(U$1-ADC1-PadP39)") (class "Default")
      (node (ref "U$1") (pin "P39") (pinfunction "ADC1_P39") (pintype "bidirectional"))
    )
    (net (code "81") (name "unconnected-(U$1-ADC2-PadP40)") (class "Default")
      (node (ref "U$1") (pin "P40") (pinfunction "ADC2_P40") (pintype "bidirectional"))
    )
    (net (code "82") (name "unconnected-(U$1-ADC3-PadP41)") (class "Default")
      (node (ref "U$1") (pin "P41") (pinfunction "ADC3_P41") (pintype "bidirectional"))
    )
    (net (code "83") (name "unconnected-(U$1-GPIO0-PadP2)") (class "Default")
      (node (ref "U$1") (pin "P2") (pinfunction "GPIO0_P2") (pintype "bidirectional"))
    )
    (net (code "84") (name "unconnected-(U$1-GPIO1-PadP3)") (class "Default")
      (node (ref "U$1") (pin "P3") (pinfunction "GPIO1_P3") (pintype "bidirectional"))
    )
    (net (code "85") (name "unconnected-(U$1-GPIO2-PadP4)") (class "Default")
      (node (ref "U$1") (pin "P4") (pinfunction "GPIO2_P4") (pintype "bidirectional"))
    )
    (net (code "86") (name "unconnected-(U$1-GPIO3-PadP5)") (class "Default")
      (node (ref "U$1") (pin "P5") (pinfunction "GPIO3_P5") (pintype "bidirectional"))
    )
    (net (code "87") (name "unconnected-(U$1-GPIO4-PadP6)") (class "Default")
      (node (ref "U$1") (pin "P6") (pinfunction "GPIO4_P6") (pintype "bidirectional"))
    )
    (net (code "88") (name "unconnected-(U$1-GPIO5-PadP7)") (class "Default")
      (node (ref "U$1") (pin "P7") (pinfunction "GPIO5_P7") (pintype "bidirectional"))
    )
    (net (code "89") (name "unconnected-(U$1-GPIO6-PadP8)") (class "Default")
      (node (ref "U$1") (pin "P8") (pinfunction "GPIO6_P8") (pintype "bidirectional"))
    )
    (net (code "90") (name "unconnected-(U$1-GPIO7-PadP9)") (class "Default")
      (node (ref "U$1") (pin "P9") (pinfunction "GPIO7_P9") (pintype "bidirectional"))
    )
    (net (code "91") (name "unconnected-(U$1-GPIO8-PadP11)") (class "Default")
      (node (ref "U$1") (pin "P11") (pinfunction "GPIO8_P11") (pintype "bidirectional"))
    )
    (net (code "92") (name "unconnected-(U$1-GPIO9-PadP12)") (class "Default")
      (node (ref "U$1") (pin "P12") (pinfunction "GPIO9_P12") (pintype "bidirectional"))
    )
    (net (code "93") (name "unconnected-(U$1-GPIO10-PadP13)") (class "Default")
      (node (ref "U$1") (pin "P13") (pinfunction "GPIO10_P13") (pintype "bidirectional"))
    )
    (net (code "94") (name "unconnected-(U$1-GPIO11-PadP14)") (class "Default")
      (node (ref "U$1") (pin "P14") (pinfunction "GPIO11_P14") (pintype "bidirectional"))
    )
    (net (code "95") (name "unconnected-(U$1-GPIO16-PadP27)") (class "Default")
      (node (ref "U$1") (pin "P27") (pinfunction "GPIO16_P27") (pintype "bidirectional"))
    )
    (net (code "96") (name "unconnected-(U$1-GPIO17-PadP28)") (class "Default")
      (node (ref "U$1") (pin "P28") (pinfunction "GPIO17_P28") (pintype "bidirectional"))
    )
    (net (code "97") (name "unconnected-(U$1-GPIO19-PadP30)") (class "Default")
      (node (ref "U$1") (pin "P30") (pinfunction "GPIO19_P30") (pintype "bidirectional"))
    )
    (net (code "98") (name "unconnected-(U$1-GPIO20-PadP31)") (class "Default")
      (node (ref "U$1") (pin "P31") (pinfunction "GPIO20_P31") (pintype "bidirectional"))
    )
    (net (code "99") (name "unconnected-(U$1-GPIO21-PadP32)") (class "Default")
      (node (ref "U$1") (pin "P32") (pinfunction "GPIO21_P32") (pintype "bidirectional"))
    )
    (net (code "100") (name "unconnected-(U$1-GPIO22-PadP34)") (class "Default")
      (node (ref "U$1") (pin "P34") (pinfunction "GPIO22_P34") (pintype "bidirectional"))
    )
    (net (code "101") (name "unconnected-(U$1-GPIO23-PadP35)") (class "Default")
      (node (ref "U$1") (pin "P35") (pinfunction "GPIO23_P35") (pintype "bidirectional"))
    )
    (net (code "102") (name "unconnected-(U$1-GPIO24-PadP36)") (class "Default")
      (node (ref "U$1") (pin "P36") (pinfunction "GPIO24_P36") (pintype "bidirectional"))
    )
    (net (code "103") (name "unconnected-(U$1-GPIO25-PadP37)") (class "Default")
      (node (ref "U$1") (pin "P37") (pinfunction "GPIO25_P37") (pintype "bidirectional"))
    )
    (net (code "104") (name "unconnected-(U$1-SWCLK-PadP24)") (class "Default")
      (node (ref "U$1") (pin "P24") (pinfunction "SWCLK_P24") (pintype "bidirectional"))
    )
    (net (code "105") (name "unconnected-(U$1-SWDIO-PadP25)") (class "Default")
      (node (ref "U$1") (pin "P25") (pinfunction "SWDIO_P25") (pintype "bidirectional"))
    )
    (net (code "106") (name "unconnected-(U2-NC-Pad4)") (class "Default")
      (node (ref "U2") (pin "4") (pinfunction "NC_4") (pintype "no_connect"))
    )
  )
)
